# usb-power-switch.net
KiCad netlist of a schematic drawn in EAGLE
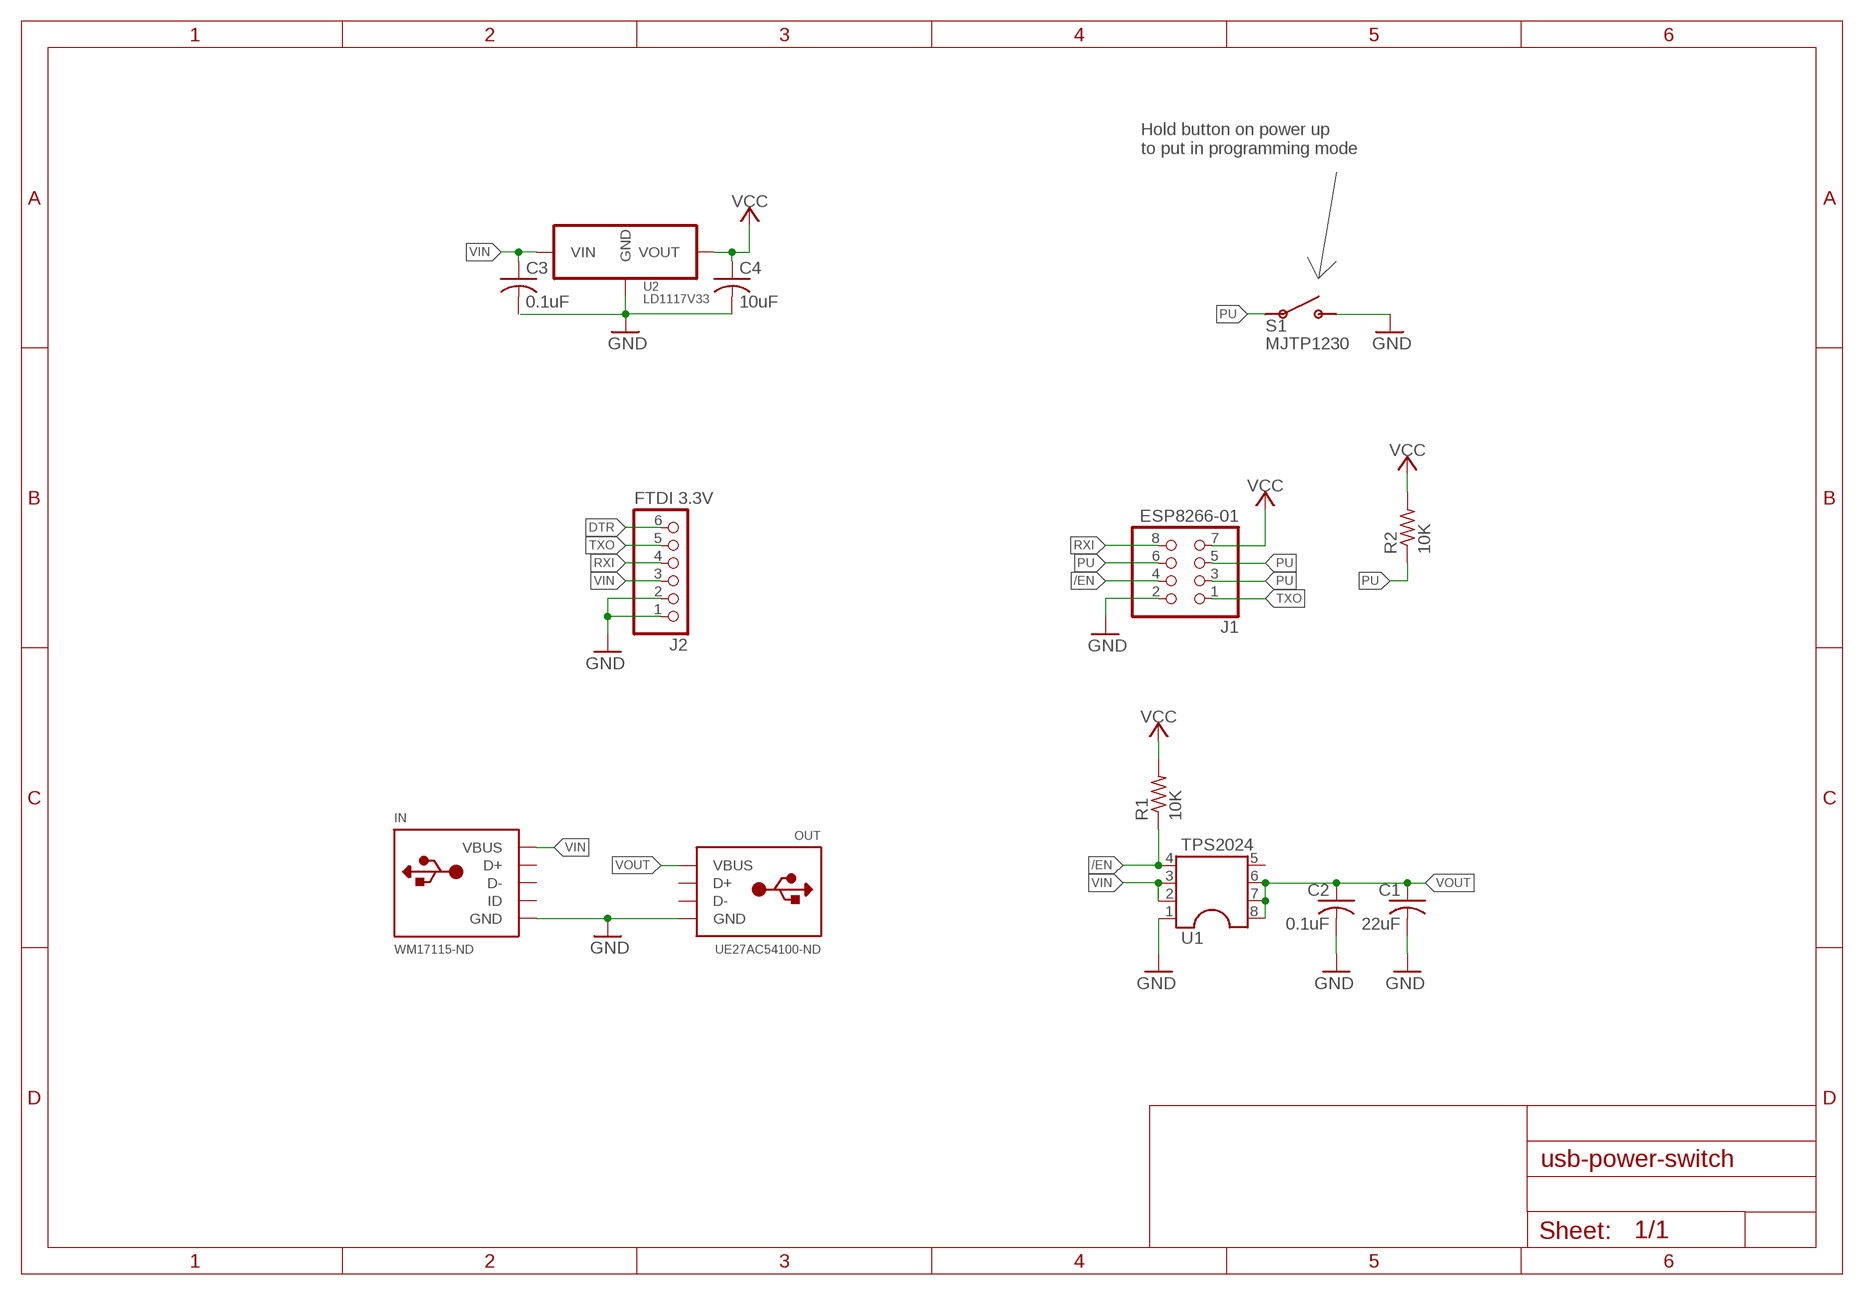
[diagram p0: schematic, sheet 1]

(export (version "E")
  (design (tool "Eeschema 10.0.6"))
  (components
    (comp (ref "C1")
      (value "22uF")
      (footprint "eagle-import:C025-025X050")
      (libsource (lib "eagle-import") (part "C-US025-025X050"))
    )
    (comp (ref "C2")
      (value "0.1uF")
      (footprint "eagle-import:C025-025X050")
      (libsource (lib "eagle-import") (part "C-US025-025X050"))
    )
    (comp (ref "C3")
      (value "0.1uF")
      (footprint "eagle-import:C025-025X050")
      (libsource (lib "eagle-import") (part "C-US025-025X050"))
    )
    (comp (ref "C4")
      (value "10uF")
      (footprint "eagle-import:C025-025X050")
      (libsource (lib "eagle-import") (part "C-US025-025X050"))
    )
    (comp (ref "IN")
      (value "WM17115-ND")
      (footprint "eagle-import:USB-MINI-B")
      (libsource (lib "eagle-import") (part "USB-MINI-B"))
    )
    (comp (ref "J1")
      (value "ESP8266-01")
      (footprint "eagle-import:2X04")
      (libsource (lib "eagle-import") (part "PINHD-2X4"))
    )
    (comp (ref "J2")
      (value "FTDI 3.3V")
      (footprint "eagle-import:1X06")
      (libsource (lib "eagle-import") (part "PINHD-1X6"))
    )
    (comp (ref "OUT")
      (value "UE27AC54100-ND")
      (footprint "eagle-import:USB-A")
      (libsource (lib "eagle-import") (part "USB-A"))
    )
    (comp (ref "R1")
      (value "10K")
      (footprint "eagle-import:0207_10")
      (libsource (lib "eagle-import") (part "R-US_0207/10"))
    )
    (comp (ref "R2")
      (value "10K")
      (footprint "eagle-import:0207_10")
      (libsource (lib "eagle-import") (part "R-US_0207/10"))
    )
    (comp (ref "S1")
      (value "MJTP1230")
      (footprint "eagle-import:TACTILE-BUTTON-MJTP1230")
      (libsource (lib "eagle-import") (part "TACTILE-BUTTON-MJTP1230"))
    )
    (comp (ref "U1")
      (value "TPS2024")
      (footprint "eagle-import:DIL08")
      (libsource (lib "eagle-import") (part "DIL8"))
    )
    (comp (ref "U2")
      (value "LD1117V33")
      (footprint "eagle-import:TO-220")
      (libsource (lib "eagle-import") (part "LD1117"))
    )
  )
  (nets
    (net (code "1") (name "DTR") (class "Default")
      (node (ref "J2") (pin "6") (pinfunction "6_6") (pintype "passive"))
    )
    (net (code "2") (name "GND") (class "Default")
      (node (ref "C1") (pin "2") (pinfunction "2_2") (pintype "passive"))
      (node (ref "C2") (pin "2") (pinfunction "2_2") (pintype "passive"))
      (node (ref "C4") (pin "2") (pinfunction "2_2") (pintype "passive"))
      (node (ref "IN") (pin "GND") (pinfunction "GND_GND") (pintype "power_in"))
      (node (ref "IN") (pin "GND1") (pinfunction "GND_GND1") (pintype "power_in"))
      (node (ref "IN") (pin "GND4") (pinfunction "GND_GND4") (pintype "power_in"))
      (node (ref "J1") (pin "2") (pinfunction "2_2") (pintype "passive"))
      (node (ref "J2") (pin "1") (pinfunction "1_1") (pintype "passive"))
      (node (ref "J2") (pin "2") (pinfunction "2_2") (pintype "passive"))
      (node (ref "OUT") (pin "P$4") (pinfunction "GND_P$4") (pintype "power_in"))
      (node (ref "OUT") (pin "P$5") (pinfunction "GND_P$5") (pintype "power_in"))
      (node (ref "OUT") (pin "P$6") (pinfunction "GND_P$6") (pintype "power_in"))
      (node (ref "S1") (pin "P$2") (pinfunction "3_P$2") (pintype "passive"))
      (node (ref "S1") (pin "P$4") (pinfunction "3_P$4") (pintype "passive"))
      (node (ref "U1") (pin "1") (pinfunction "1_1") (pintype "passive"))
      (node (ref "U2") (pin "P$1") (pinfunction "GND_P$1") (pintype "power_in"))
    )
    (net (code "3") (name "PU") (class "Default")
      (node (ref "J1") (pin "3") (pinfunction "3_3") (pintype "passive"))
      (node (ref "J1") (pin "5") (pinfunction "5_5") (pintype "passive"))
      (node (ref "J1") (pin "6") (pinfunction "6_6") (pintype "passive"))
      (node (ref "R2") (pin "1") (pinfunction "1_1") (pintype "passive"))
      (node (ref "S1") (pin "P$1") (pinfunction "1_P$1") (pintype "passive"))
      (node (ref "S1") (pin "P$3") (pinfunction "1_P$3") (pintype "passive"))
    )
    (net (code "4") (name "RXI") (class "Default")
      (node (ref "J1") (pin "8") (pinfunction "8_8") (pintype "passive"))
      (node (ref "J2") (pin "4") (pinfunction "4_4") (pintype "passive"))
    )
    (net (code "5") (name "TXO") (class "Default")
      (node (ref "J1") (pin "1") (pinfunction "1_1") (pintype "passive"))
      (node (ref "J2") (pin "5") (pinfunction "5_5") (pintype "passive"))
    )
    (net (code "6") (name "VCC") (class "Default")
      (node (ref "C4") (pin "1") (pinfunction "1_1") (pintype "passive"))
      (node (ref "J1") (pin "7") (pinfunction "7_7") (pintype "passive"))
      (node (ref "R1") (pin "2") (pinfunction "2_2") (pintype "passive"))
      (node (ref "R2") (pin "2") (pinfunction "2_2") (pintype "passive"))
      (node (ref "U2") (pin "P$2") (pinfunction "VOUT_P$2") (pintype "output"))
      (node (ref "U2") (pin "P$4") (pinfunction "VOUT_P$4") (pintype "output"))
    )
    (net (code "7") (name "VIN") (class "Default")
      (node (ref "C3") (pin "1") (pinfunction "1_1") (pintype "passive"))
      (node (ref "IN") (pin "VBUS") (pinfunction "VBUS_VBUS") (pintype "power_in"))
      (node (ref "J2") (pin "3") (pinfunction "3_3") (pintype "passive"))
      (node (ref "U1") (pin "2") (pinfunction "2_2") (pintype "passive"))
      (node (ref "U1") (pin "3") (pinfunction "3_3") (pintype "passive"))
      (node (ref "U2") (pin "P$3") (pinfunction "VIN_P$3") (pintype "input"))
    )
    (net (code "8") (name "VOUT") (class "Default")
      (node (ref "C1") (pin "1") (pinfunction "1_1") (pintype "passive"))
      (node (ref "C2") (pin "1") (pinfunction "1_1") (pintype "passive"))
      (node (ref "OUT") (pin "P$1") (pinfunction "VBUS_P$1") (pintype "power_in"))
      (node (ref "U1") (pin "6") (pinfunction "6_6") (pintype "passive"))
      (node (ref "U1") (pin "7") (pinfunction "7_7") (pintype "passive"))
      (node (ref "U1") (pin "8") (pinfunction "8_8") (pintype "passive"))
    )
    (net (code "9") (name "unconnected-(C3-Pad2)") (class "Default")
      (node (ref "C3") (pin "2") (pinfunction "2_2") (pintype "passive"))
    )
    (net (code "10") (name "unconnected-(IN-PadD+)") (class "Default")
      (node (ref "IN") (pin "D+") (pinfunction "D+_D+") (pintype "bidirectional"))
    )
    (net (code "11") (name "unconnected-(IN-PadD-)") (class "Default")
      (node (ref "IN") (pin "D-") (pinfunction "D-_D-") (pintype "bidirectional"))
    )
    (net (code "12") (name "unconnected-(IN-PadID)") (class "Default")
      (node (ref "IN") (pin "ID") (pinfunction "ID_ID") (pintype "bidirectional"))
    )
    (net (code "13") (name "unconnected-(OUT-D+-PadP$3)") (class "Default")
      (node (ref "OUT") (pin "P$3") (pinfunction "D+_P$3") (pintype "bidirectional"))
    )
    (net (code "14") (name "unconnected-(OUT-D--PadP$2)") (class "Default")
      (node (ref "OUT") (pin "P$2") (pinfunction "D-_P$2") (pintype "bidirectional"))
    )
    (net (code "15") (name "unconnected-(U1-Pad5)") (class "Default")
      (node (ref "U1") (pin "5") (pinfunction "5_5") (pintype "passive"))
    )
    (net (code "16") (name "{slash}EN") (class "Default")
      (node (ref "J1") (pin "4") (pinfunction "4_4") (pintype "passive"))
      (node (ref "R1") (pin "1") (pinfunction "1_1") (pintype "passive"))
      (node (ref "U1") (pin "4") (pinfunction "4_4") (pintype "passive"))
    )
  )
)
